# mp28164-buck-boost-flashlight-driver-tes.net
KiCad netlist of a schematic drawn in EAGLE
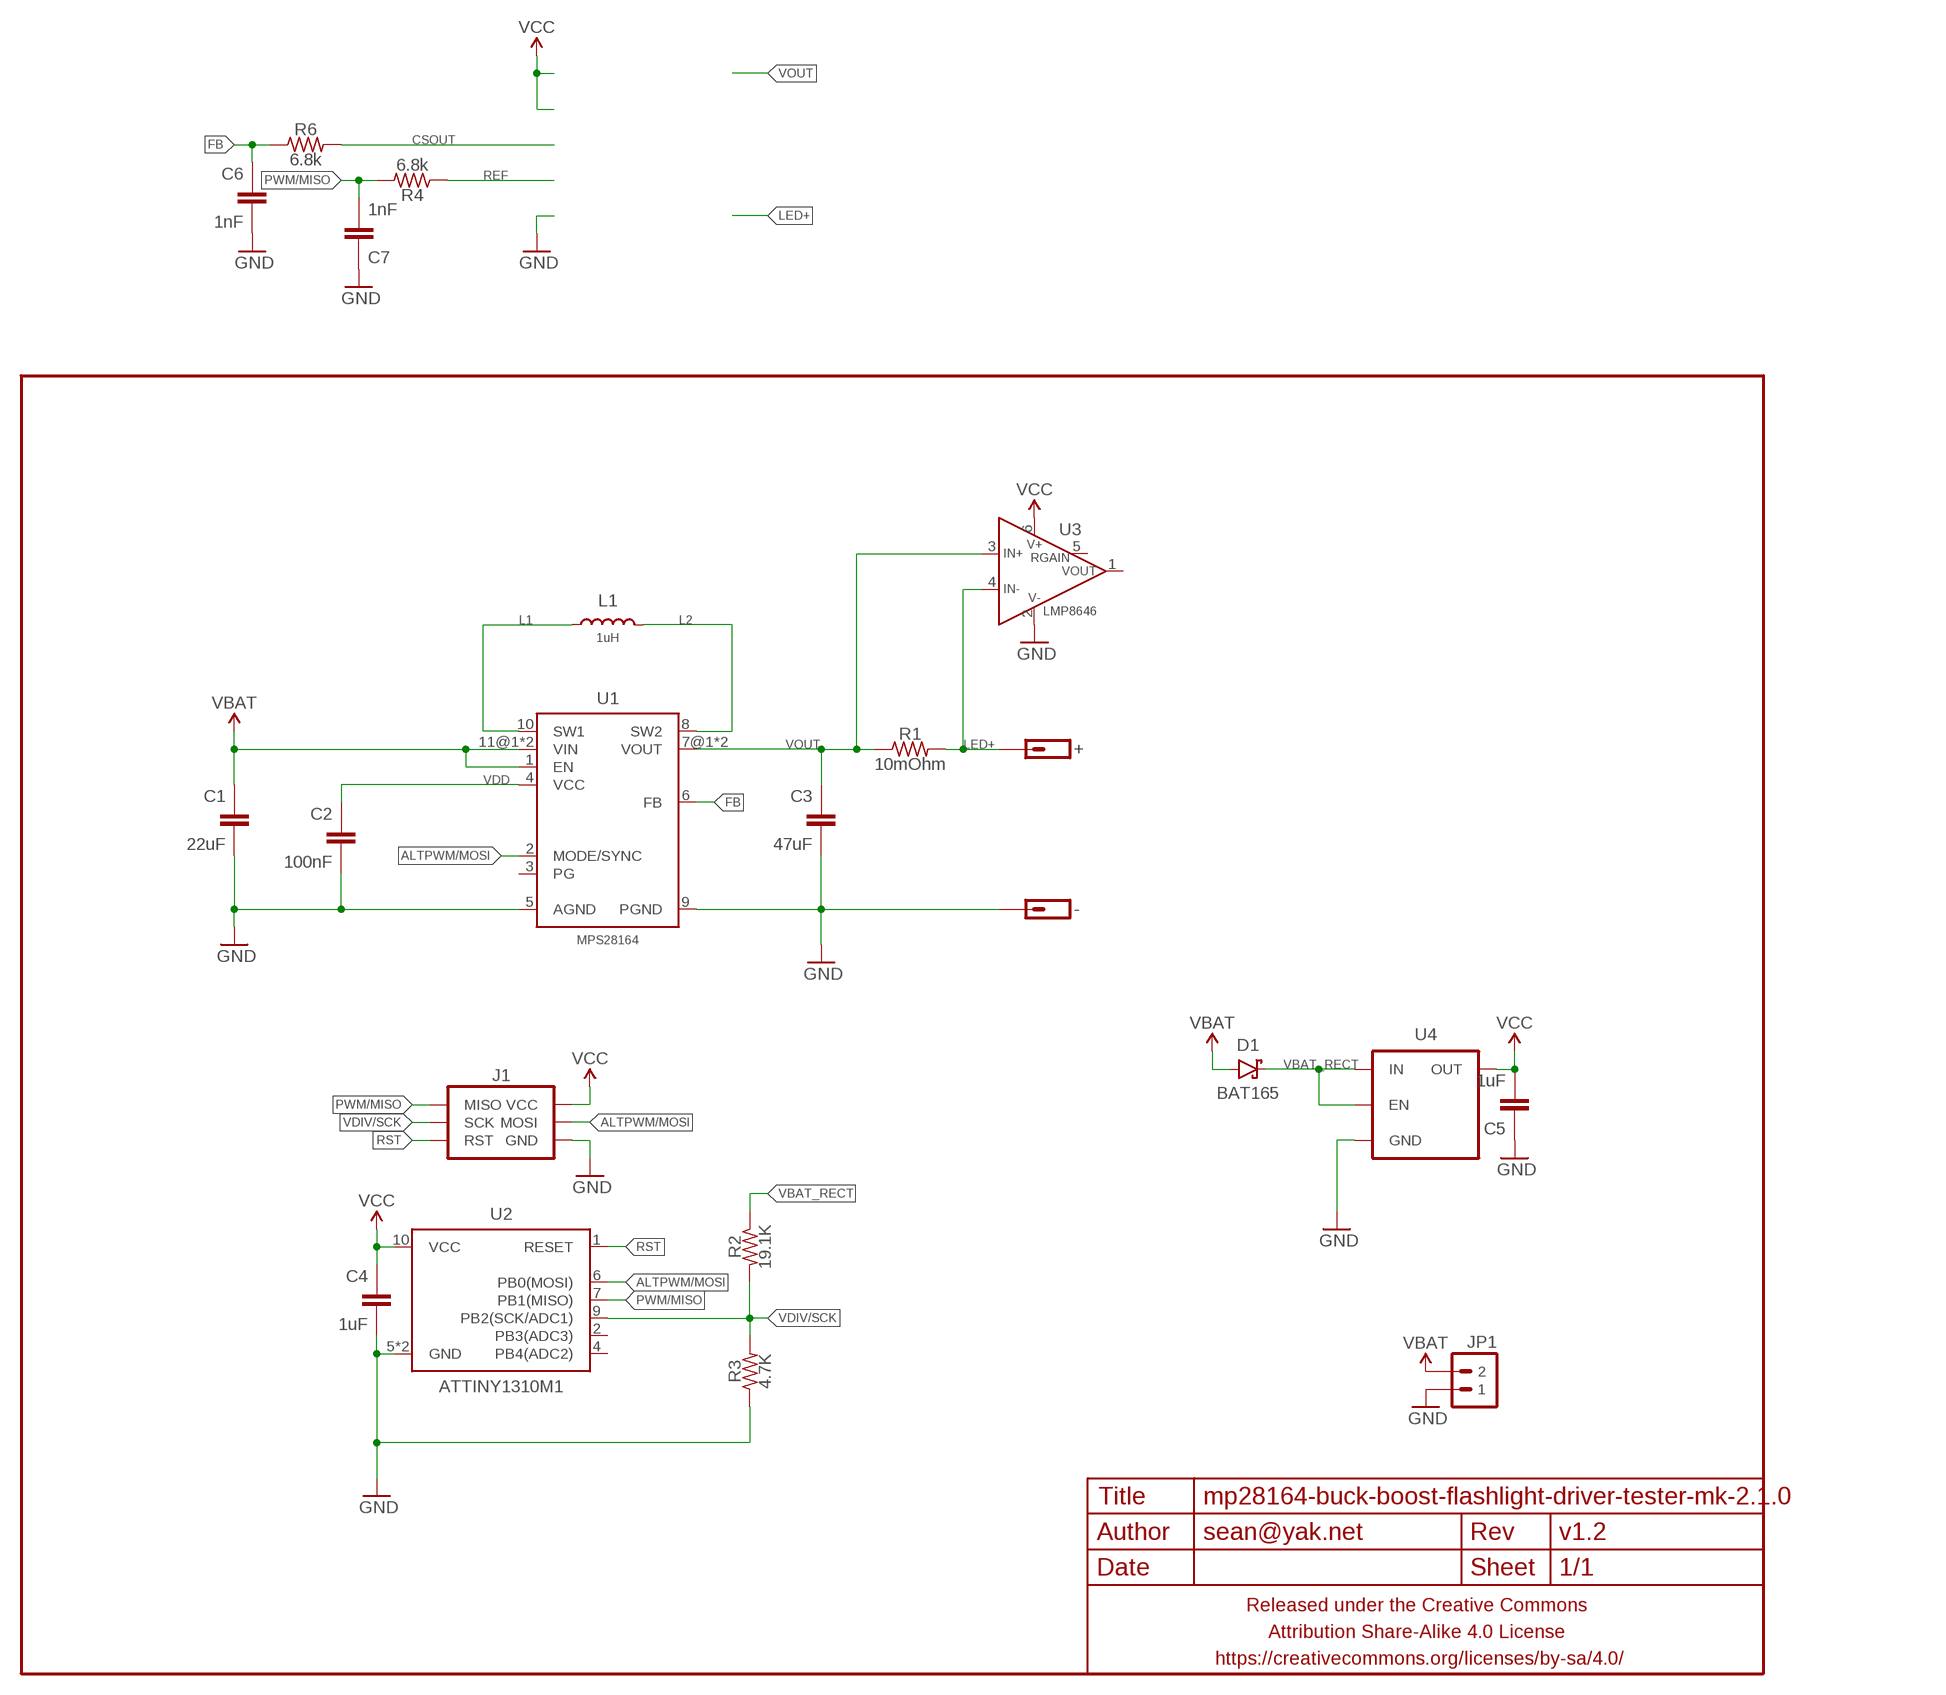
[diagram p0: schematic, sheet 1]

(export (version "E")
  (design (tool "Eeschema 10.0.6"))
  (components
    (comp (ref "+")
      (value "M01PTH-1.2MM-NS")
      (footprint "eagle-import:1X01-1.2MM-NS")
      (libsource (lib "eagle-import") (part "M01PTH-1.2MM-NS"))
    )
    (comp (ref "-")
      (value "M01PTH-1.2MM-NS")
      (footprint "eagle-import:1X01-1.2MM-NS")
      (libsource (lib "eagle-import") (part "M01PTH-1.2MM-NS"))
    )
    (comp (ref "C1")
      (value "22uF")
      (footprint "eagle-import:C1206")
      (libsource (lib "eagle-import") (part "CAPACITOR-CERAMICC1206"))
    )
    (comp (ref "C2")
      (value "100nF")
      (footprint "eagle-import:C0402")
      (libsource (lib "eagle-import") (part "CAPACITOR-CERAMICC0402"))
    )
    (comp (ref "C3")
      (value "47uF")
      (footprint "eagle-import:C1206")
      (libsource (lib "eagle-import") (part "CAPACITOR-CERAMICC1206"))
    )
    (comp (ref "C4")
      (value "1uF")
      (footprint "eagle-import:C0402")
      (libsource (lib "eagle-import") (part "CAPACITOR-CERAMICC0402"))
    )
    (comp (ref "C5")
      (value "1uF")
      (footprint "eagle-import:C0402")
      (libsource (lib "eagle-import") (part "CAPACITOR-CERAMICC0402"))
    )
    (comp (ref "C6")
      (value "1nF")
      (footprint "eagle-import:C0402")
      (libsource (lib "eagle-import") (part "CAPACITOR-CERAMICC0402"))
    )
    (comp (ref "C7")
      (value "1nF")
      (footprint "eagle-import:C0402")
      (libsource (lib "eagle-import") (part "CAPACITOR-CERAMICC0402"))
    )
    (comp (ref "D1")
      (value "BAT165")
      (footprint "eagle-import:SOD323-SCHOTTKY")
      (libsource (lib "eagle-import") (part "DIODE-SCHOTTKYSOD323"))
    )
    (comp (ref "FRAME1")
      (value "FRAME-LETTERNO_PACKAGE")
      (footprint "eagle-import:DUMMY")
      (fields
        (field (name "DESIGNER") "Nobody")
        (field (name "VERSION") "v01")
        (field (name "DESIGNER_1") "sean@yak.net")
        (field (name "VERSION_1") "v1.2")
      )
      (libsource (lib "eagle-import") (part "FRAME-LETTERNO_PACKAGE"))
    )
    (comp (ref "J1")
      (value "AVR_SPI_PRG_6PTH")
      (footprint "eagle-import:2X3")
      (libsource (lib "eagle-import") (part "AVR_SPI_PRG_6PTH"))
    )
    (comp (ref "JP1")
      (value "M02PTH-CENTERED")
      (footprint "eagle-import:1X02-CENTER")
      (libsource (lib "eagle-import") (part "M02PTH-CENTERED"))
    )
    (comp (ref "L1")
      (value "1uH")
      (footprint "eagle-import:XAL60XX")
      (libsource (lib "eagle-import") (part "INDUCTORXAL60XX"))
    )
    (comp (ref "R1")
      (value "10mOhm")
      (footprint "eagle-import:R1206")
      (libsource (lib "eagle-import") (part "RESISTORR1206"))
    )
    (comp (ref "R2")
      (value "19.1K")
      (footprint "eagle-import:R0402")
      (libsource (lib "eagle-import") (part "RESISTORR0402"))
    )
    (comp (ref "R3")
      (value "4.7K")
      (footprint "eagle-import:R0402")
      (libsource (lib "eagle-import") (part "RESISTORR0402"))
    )
    (comp (ref "R4")
      (value "6.8k")
      (footprint "eagle-import:R0402")
      (libsource (lib "eagle-import") (part "RESISTORR0402"))
    )
    (comp (ref "R6")
      (value "6.8k")
      (footprint "eagle-import:R0402")
      (libsource (lib "eagle-import") (part "RESISTORR0402"))
    )
    (comp (ref "U1")
      (value "MPS28164")
      (footprint "eagle-import:MPS28164")
      (libsource (lib "eagle-import") (part "MPS28164"))
    )
    (comp (ref "U2")
      (value "ATTINY1310M1")
      (footprint "eagle-import:QFN10(2X5)")
      (libsource (lib "eagle-import") (part "ATTINY1310M1"))
    )
    (comp (ref "U3")
      (value "LMP8646")
      (footprint "eagle-import:SOT23-6")
      (libsource (lib "eagle-import") (part "LMP8646"))
    )
    (comp (ref "U4")
      (value "V_REG_ENTLV700")
      (footprint "eagle-import:SC70")
      (libsource (lib "eagle-import") (part "V_REG_ENTLV700"))
    )
  )
  (nets
    (net (code "1") (name "/CSOUT") (class "Default")
      (node (ref "R6") (pin "2") (pinfunction "2_2") (pintype "passive"))
    )
    (net (code "2") (name "/L1") (class "Default")
      (node (ref "L1") (pin "P$1") (pinfunction "1_P$1") (pintype "passive"))
      (node (ref "U1") (pin "10") (pinfunction "SW1_10") (pintype "bidirectional"))
    )
    (net (code "3") (name "/L2") (class "Default")
      (node (ref "L1") (pin "P$2") (pinfunction "2_P$2") (pintype "passive"))
      (node (ref "U1") (pin "8") (pinfunction "SW2_8") (pintype "bidirectional"))
    )
    (net (code "4") (name "/REF") (class "Default")
      (node (ref "R4") (pin "1") (pinfunction "1_1") (pintype "passive"))
    )
    (net (code "5") (name "/VDD") (class "Default")
      (node (ref "C2") (pin "1") (pinfunction "1_1") (pintype "passive"))
      (node (ref "U1") (pin "4") (pinfunction "VCC_4") (pintype "bidirectional"))
    )
    (net (code "6") (name "ALTPWM{slash}MOSI") (class "Default")
      (node (ref "J1") (pin "4") (pinfunction "MOSI_4") (pintype "passive"))
      (node (ref "U1") (pin "2") (pinfunction "MODE/SYNC_2") (pintype "bidirectional"))
      (node (ref "U2") (pin "6") (pinfunction "PB0(MOSI)_6") (pintype "bidirectional"))
    )
    (net (code "7") (name "FB") (class "Default")
      (node (ref "C6") (pin "1") (pinfunction "1_1") (pintype "passive"))
      (node (ref "R6") (pin "1") (pinfunction "1_1") (pintype "passive"))
      (node (ref "U1") (pin "6") (pinfunction "FB_6") (pintype "bidirectional"))
    )
    (net (code "8") (name "GND") (class "Default")
      (node (ref "-") (pin "P$1") (pinfunction "1_P$1") (pintype "passive"))
      (node (ref "C1") (pin "2") (pinfunction "2_2") (pintype "passive"))
      (node (ref "C2") (pin "2") (pinfunction "2_2") (pintype "passive"))
      (node (ref "C3") (pin "2") (pinfunction "2_2") (pintype "passive"))
      (node (ref "C4") (pin "2") (pinfunction "2_2") (pintype "passive"))
      (node (ref "C5") (pin "1") (pinfunction "1_1") (pintype "passive"))
      (node (ref "C6") (pin "2") (pinfunction "2_2") (pintype "passive"))
      (node (ref "C7") (pin "1") (pinfunction "1_1") (pintype "passive"))
      (node (ref "J1") (pin "6") (pinfunction "GND_6") (pintype "passive"))
      (node (ref "JP1") (pin "1") (pinfunction "1_1") (pintype "passive"))
      (node (ref "R3") (pin "1") (pinfunction "1_1") (pintype "passive"))
      (node (ref "U1") (pin "5") (pinfunction "AGND_5") (pintype "bidirectional"))
      (node (ref "U1") (pin "9") (pinfunction "PGND_9") (pintype "bidirectional"))
      (node (ref "U2") (pin "5") (pinfunction "GND_5") (pintype "bidirectional"))
      (node (ref "U2") (pin "PAD") (pinfunction "GND_PAD") (pintype "bidirectional"))
      (node (ref "U3") (pin "2") (pinfunction "V-_2") (pintype "bidirectional"))
      (node (ref "U4") (pin "2") (pinfunction "GND_2") (pintype "input"))
    )
    (net (code "9") (name "LED+") (class "Default")
      (node (ref "+") (pin "P$1") (pinfunction "1_P$1") (pintype "passive"))
      (node (ref "R1") (pin "2") (pinfunction "2_2") (pintype "passive"))
      (node (ref "U3") (pin "4") (pinfunction "IN-_4") (pintype "bidirectional"))
    )
    (net (code "10") (name "PWM{slash}MISO") (class "Default")
      (node (ref "C7") (pin "2") (pinfunction "2_2") (pintype "passive"))
      (node (ref "J1") (pin "1") (pinfunction "MISO_1") (pintype "passive"))
      (node (ref "R4") (pin "2") (pinfunction "2_2") (pintype "passive"))
      (node (ref "U2") (pin "7") (pinfunction "PB1(MISO)_7") (pintype "bidirectional"))
    )
    (net (code "11") (name "RST") (class "Default")
      (node (ref "J1") (pin "5") (pinfunction "RST_5") (pintype "passive"))
      (node (ref "U2") (pin "1") (pinfunction "RESET_1") (pintype "bidirectional"))
    )
    (net (code "12") (name "VBAT") (class "Default")
      (node (ref "C1") (pin "1") (pinfunction "1_1") (pintype "passive"))
      (node (ref "D1") (pin "A") (pinfunction "A_A") (pintype "passive"))
      (node (ref "JP1") (pin "2") (pinfunction "2_2") (pintype "passive"))
      (node (ref "U1") (pin "1") (pinfunction "EN_1") (pintype "bidirectional"))
      (node (ref "U1") (pin "11@1") (pinfunction "VIN_11@1") (pintype "bidirectional"))
      (node (ref "U1") (pin "11@2") (pinfunction "VIN_11@2") (pintype "bidirectional"))
    )
    (net (code "13") (name "VBAT_RECT") (class "Default")
      (node (ref "D1") (pin "C") (pinfunction "C_C") (pintype "passive"))
      (node (ref "R2") (pin "1") (pinfunction "1_1") (pintype "passive"))
      (node (ref "U4") (pin "1") (pinfunction "IN_1") (pintype "input"))
      (node (ref "U4") (pin "3") (pinfunction "EN_3") (pintype "input"))
    )
    (net (code "14") (name "VCC") (class "Default")
      (node (ref "C4") (pin "1") (pinfunction "1_1") (pintype "passive"))
      (node (ref "C5") (pin "2") (pinfunction "2_2") (pintype "passive"))
      (node (ref "J1") (pin "2") (pinfunction "VCC_2") (pintype "passive"))
      (node (ref "U2") (pin "10") (pinfunction "VCC_10") (pintype "bidirectional"))
      (node (ref "U3") (pin "6") (pinfunction "V+_6") (pintype "bidirectional"))
      (node (ref "U4") (pin "5") (pinfunction "OUT_5") (pintype "passive"))
    )
    (net (code "15") (name "VDIV{slash}SCK") (class "Default")
      (node (ref "J1") (pin "3") (pinfunction "SCK_3") (pintype "passive"))
      (node (ref "R2") (pin "2") (pinfunction "2_2") (pintype "passive"))
      (node (ref "R3") (pin "2") (pinfunction "2_2") (pintype "passive"))
      (node (ref "U2") (pin "9") (pinfunction "PB2(SCK/ADC1)_9") (pintype "bidirectional"))
    )
    (net (code "16") (name "VOUT") (class "Default")
      (node (ref "C3") (pin "1") (pinfunction "1_1") (pintype "passive"))
      (node (ref "R1") (pin "1") (pinfunction "1_1") (pintype "passive"))
      (node (ref "U1") (pin "7@1") (pinfunction "VOUT_7@1") (pintype "bidirectional"))
      (node (ref "U1") (pin "7@2") (pinfunction "VOUT_7@2") (pintype "bidirectional"))
      (node (ref "U3") (pin "3") (pinfunction "IN+_3") (pintype "bidirectional"))
    )
    (net (code "17") (name "unconnected-(U1-PG-Pad3)") (class "Default")
      (node (ref "U1") (pin "3") (pinfunction "PG_3") (pintype "bidirectional"))
    )
    (net (code "18") (name "unconnected-(U2-PB3(ADC3)-Pad2)") (class "Default")
      (node (ref "U2") (pin "2") (pinfunction "PB3(ADC3)_2") (pintype "bidirectional"))
    )
    (net (code "19") (name "unconnected-(U2-PB4(ADC2)-Pad4)") (class "Default")
      (node (ref "U2") (pin "4") (pinfunction "PB4(ADC2)_4") (pintype "bidirectional"))
    )
    (net (code "20") (name "unconnected-(U3-RGAIN-Pad5)") (class "Default")
      (node (ref "U3") (pin "5") (pinfunction "RGAIN_5") (pintype "bidirectional"))
    )
    (net (code "21") (name "unconnected-(U3-VOUT-Pad1)") (class "Default")
      (node (ref "U3") (pin "1") (pinfunction "VOUT_1") (pintype "bidirectional"))
    )
  )
)
